# iv_sensing.net
KiCad netlist of a schematic drawn in Altium Designer
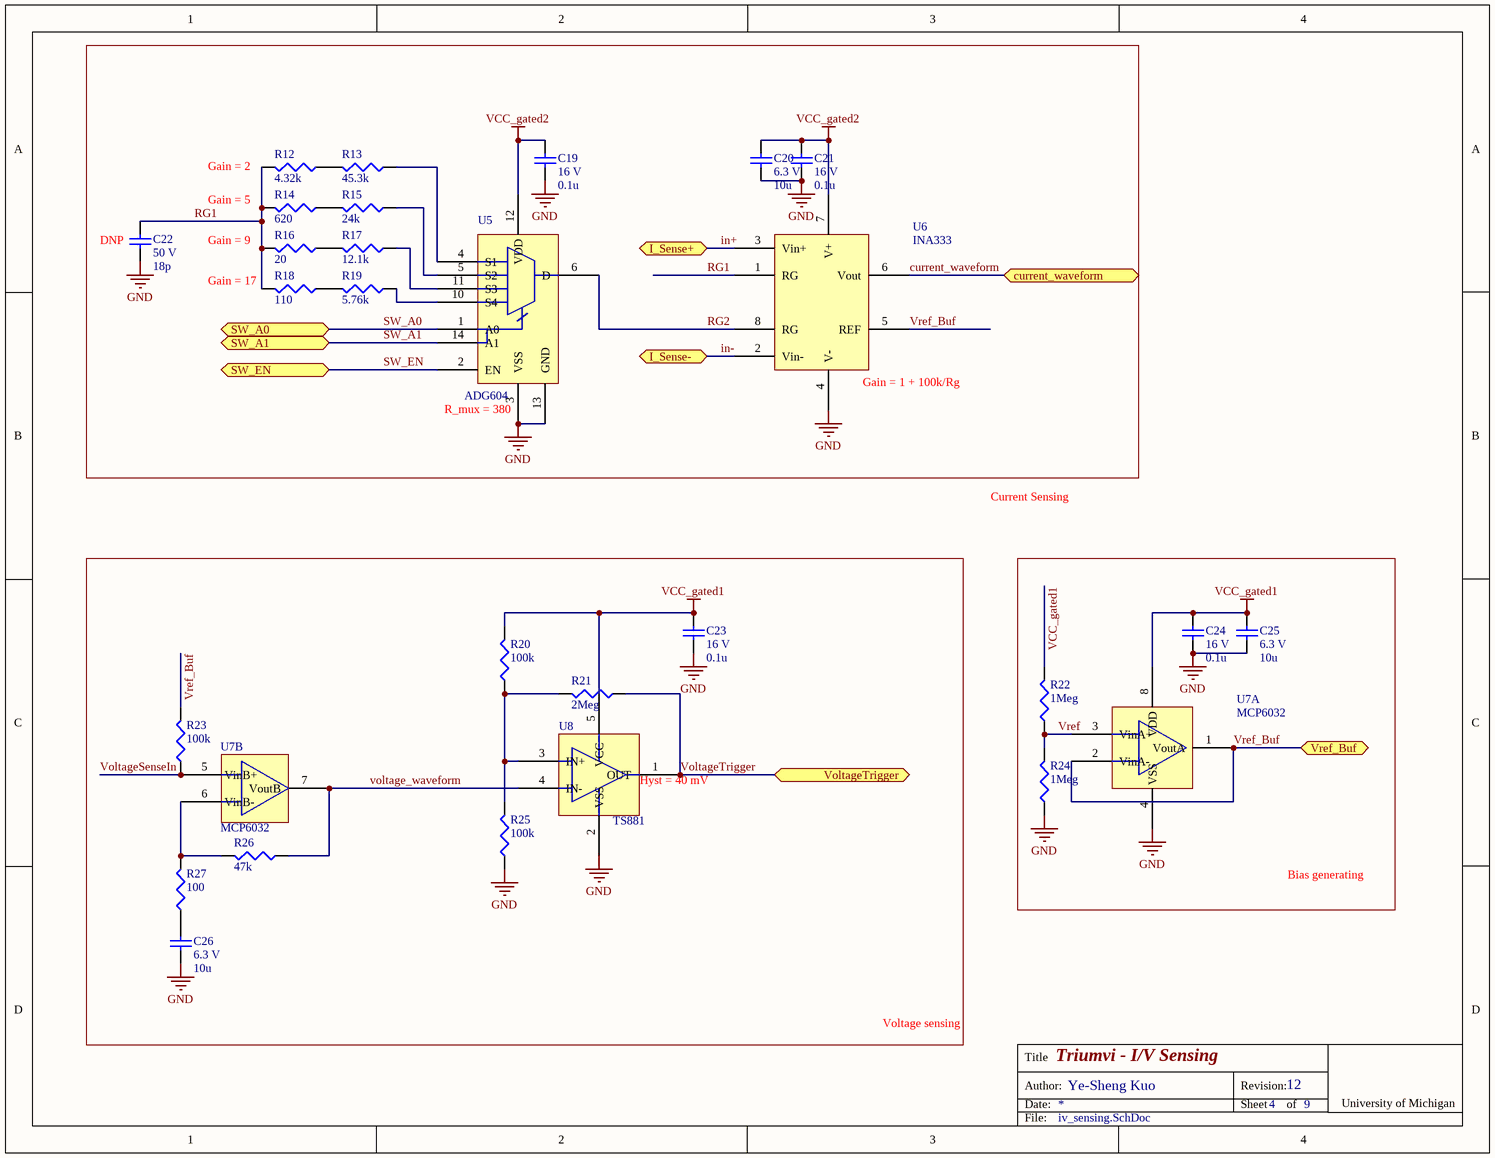
[diagram p0: iv_sensing.SchDoc]

(export (version "E")
  (design (tool "Eeschema 10.0.6"))
  (components
    (comp (ref "C19")
      (value "0.1u")
      (footprint "0402")
      (description "0.10µF ±10% 16V Ceramic Capacitor X7R 0402")
      (fields
        (field (name "VOLTAGE RATED") "16 V")
        (field (name "TOLERANCE") "10%")
        (field (name "MANUFACTURER PART NUMBER") "GRM155R71C104KA88D")
      )
      (libsource (lib "capacitors") (part "GRM155R71C104KA88D"))
    )
    (comp (ref "C20")
      (value "10u")
      (footprint "0603")
      (description "10µF ±20% 6.3V Ceramic Capacitor X5R 0603")
      (fields
        (field (name "VOLTAGE RATED") "6.3 V")
        (field (name "TOLERANCE") "20%")
        (field (name "MANUFACTURER PART NUMBER") "C1608X5R0J106M080AB")
      )
      (libsource (lib "capacitors") (part "C1608X5R0J106M080AB"))
    )
    (comp (ref "C21")
      (value "0.1u")
      (footprint "0402")
      (description "0.10µF ±10% 16V Ceramic Capacitor X7R 0402")
      (fields
        (field (name "VOLTAGE RATED") "16 V")
        (field (name "TOLERANCE") "10%")
        (field (name "MANUFACTURER PART NUMBER") "GRM155R71C104KA88D")
      )
      (libsource (lib "capacitors") (part "GRM155R71C104KA88D"))
    )
    (comp (ref "C22")
      (value "18p")
      (footprint "0402")
      (description "18pF ±2% 50V Ceramic Capacitor C0G, NP0 0402")
      (fields
        (field (name "TOLERANCE") "2%")
        (field (name "MANUFACTURER PART NUMBER") "500R07S180GV4T")
        (field (name "VOLTAGE RATED") "50 V")
      )
      (libsource (lib "capacitors") (part "500R07S180GV4T"))
    )
    (comp (ref "C23")
      (value "0.1u")
      (footprint "0402")
      (description "0.10µF ±10% 16V Ceramic Capacitor X7R 0402")
      (fields
        (field (name "VOLTAGE RATED") "16 V")
        (field (name "TOLERANCE") "10%")
        (field (name "MANUFACTURER PART NUMBER") "GRM155R71C104KA88D")
      )
      (libsource (lib "capacitors") (part "GRM155R71C104KA88D"))
    )
    (comp (ref "C24")
      (value "0.1u")
      (footprint "0402")
      (description "0.10µF ±10% 16V Ceramic Capacitor X7R 0402")
      (fields
        (field (name "VOLTAGE RATED") "16 V")
        (field (name "TOLERANCE") "10%")
        (field (name "MANUFACTURER PART NUMBER") "GRM155R71C104KA88D")
      )
      (libsource (lib "capacitors") (part "GRM155R71C104KA88D"))
    )
    (comp (ref "C25")
      (value "10u")
      (footprint "0603")
      (description "10µF ±20% 6.3V Ceramic Capacitor X5R 0603")
      (fields
        (field (name "VOLTAGE RATED") "6.3 V")
        (field (name "TOLERANCE") "20%")
        (field (name "MANUFACTURER PART NUMBER") "C1608X5R0J106M080AB")
      )
      (libsource (lib "capacitors") (part "C1608X5R0J106M080AB"))
    )
    (comp (ref "C26")
      (value "10u")
      (footprint "0603")
      (description "10µF ±20% 6.3V Ceramic Capacitor X5R 0603")
      (fields
        (field (name "VOLTAGE RATED") "6.3 V")
        (field (name "TOLERANCE") "20%")
        (field (name "MANUFACTURER PART NUMBER") "C1608X5R0J106M080AB")
      )
      (libsource (lib "capacitors") (part "C1608X5R0J106M080AB"))
    )
    (comp (ref "R12")
      (value "4.32k")
      (footprint "0402")
      (description "RES SMD 4.32K OHM 1% 1/16W 0402")
      (fields
        (field (name "MANUFACTURER PART NUMBER") "CRCW04024K32FKED")
        (field (name "MANUFACTURER") "Vishay Dale")
      )
      (libsource (lib "resistors") (part "CRCW04024K32FKED"))
    )
    (comp (ref "R13")
      (value "45.3k")
      (footprint "0402")
      (description "RES SMD 45.3KOHM 0.5% 1/16W 0402")
      (fields
        (field (name "MANUFACTURER PART NUMBER") "RT0402DRD0745K3L")
        (field (name "MANUFACTURER") "Yageo")
      )
      (libsource (lib "resistors") (part "RT0402DRD0745K3L"))
    )
    (comp (ref "R14")
      (value "620")
      (footprint "0402")
      (description "RES SMD 620 OHM 1% 1/16W 0402")
      (fields
        (field (name "MANUFACTURER PART NUMBER") "CRCW0402620RFKED")
        (field (name "MANUFACTURER") "Vishay Dale")
      )
      (libsource (lib "resistors") (part "CRCW0402620RFKED"))
    )
    (comp (ref "R15")
      (value "24k")
      (footprint "0402")
      (description "RES SMD 24K OHM 0.5% 1/16W 0402")
      (fields
        (field (name "MANUFACTURER PART NUMBER") "RT0402DRE0724KL")
        (field (name "MANUFACTURER") "Yageo")
      )
      (libsource (lib "resistors") (part "RT0402DRE0724KL"))
    )
    (comp (ref "R16")
      (value "20")
      (footprint "0402")
      (description "RES SMD 20 OHM 1% 1/16W 0402")
      (fields
        (field (name "MANUFACTURER PART NUMBER") "CRCW040220R0FKED")
        (field (name "MANUFACTURER") "Vishay Dale")
      )
      (libsource (lib "resistors") (part "CRCW040220R0FKED"))
    )
    (comp (ref "R17")
      (value "12.1k")
      (footprint "0402")
      (description "RES SMD 12.1K OHM 1% 1/16W 0402")
      (fields
        (field (name "MANUFACTURER PART NUMBER") "CRCW040212K1FKED")
        (field (name "MANUFACTURER") "Vishay Dale")
      )
      (libsource (lib "resistors") (part "CRCW040212K1FKED"))
    )
    (comp (ref "R18")
      (value "110")
      (footprint "0402")
      (description "RES SMD 110 OHM 1% 1/16W 0402")
      (fields
        (field (name "MANUFACTURER PART NUMBER") "CRCW0402110RFKED")
        (field (name "MANUFACTURER") "Vishay Dale")
      )
      (libsource (lib "resistors") (part "CRCW0402110RFKED"))
    )
    (comp (ref "R19")
      (value "5.76k")
      (footprint "0402")
      (description "RES SMD 5.76K OHM 0.5% 1/16W 0402")
      (fields
        (field (name "MANUFACTURER PART NUMBER") "RC0402FR-075K76L")
        (field (name "MANUFACTURER") "Yageo")
      )
      (libsource (lib "resistors") (part "RC0402FR-075K76L"))
    )
    (comp (ref "R20")
      (value "100k")
      (footprint "0402")
      (description "RES SMD 100K OHM 1% 1/16W 0402")
      (fields (field (name "TOLERANCE") "1%") (field (name "POWER") "1/16 W"))
      (libsource (lib "resistors") (part "CRCW0402100KFKED"))
    )
    (comp (ref "R21")
      (value "2Meg")
      (footprint "0402")
      (description "RES SMD 2M OHM 1% 1/16W 0402")
      (fields (field (name "TOLERANCE") "1%") (field (name "POWER") "1/16 W"))
      (libsource (lib "resistors") (part "CRCW04022M00FKED"))
    )
    (comp (ref "R22")
      (value "1Meg")
      (footprint "0402")
      (description "RES SMD 1M OHM 1% 1/16W 0402")
      (fields (field (name "TOLERANCE") "1%") (field (name "POWER") "1/16 W"))
      (libsource (lib "resistors") (part "CRCW04021M00FKED"))
    )
    (comp (ref "R23")
      (value "100k")
      (footprint "0402")
      (description "RES SMD 100K OHM 1% 1/16W 0402")
      (fields (field (name "TOLERANCE") "1%") (field (name "POWER") "1/16 W"))
      (libsource (lib "resistors") (part "CRCW0402100KFKED"))
    )
    (comp (ref "R24")
      (value "1Meg")
      (footprint "0402")
      (description "RES SMD 1M OHM 1% 1/16W 0402")
      (fields (field (name "TOLERANCE") "1%") (field (name "POWER") "1/16 W"))
      (libsource (lib "resistors") (part "CRCW04021M00FKED"))
    )
    (comp (ref "R25")
      (value "100k")
      (footprint "0402")
      (description "RES SMD 100K OHM 1% 1/16W 0402")
      (fields (field (name "TOLERANCE") "1%") (field (name "POWER") "1/16 W"))
      (libsource (lib "resistors") (part "CRCW0402100KFKED"))
    )
    (comp (ref "R26")
      (value "47k")
      (footprint "0402")
      (description "RES SMD 47K OHM 1% 1/16W 0402")
      (fields (field (name "TOLERANCE") "1%") (field (name "POWER") "1/16 W"))
      (libsource (lib "resistors") (part "CRCW040247K0FKED"))
    )
    (comp (ref "R27")
      (value "100")
      (footprint "0402")
      (description "RES SMD 100 OHM 1% 1/16W 0402")
      (fields (field (name "TOLERANCE") "1%") (field (name "POWER") "1/16 W"))
      (libsource (lib "resistors") (part "CRCW0402100RFKED"))
    )
    (comp (ref "U5")
      (value "ADG604")
      (footprint "TSSOP-14")
      (description "1 pC Charge Injection, 100 pA Leakage  CMOS  5 V/5 V/3 V 4-Channel Multiplexer")
      (libsource (lib "multiplexer") (part "ADG604"))
    )
    (comp (ref "U6")
      (value "INA333")
      (footprint "MSOP-8")
      (description "Micro-Power (50uA), Zero-Drift, Rail-to-Rail Out  Instrumentation Amplifier")
      (libsource (lib "amplifier") (part "INA333"))
    )
    (comp (ref "U7")
      (value "MCP6032")
      (footprint "MSOP-8")
      (description "0.9 µA, High Precision Op Amps")
      (libsource (lib "amplifier") (part "MCP6032"))
    )
    (comp (ref "U8")
      (value "TS881")
      (footprint "SC70-5")
      (description "Rail-to-rail 0.9 V nanopower comparator")
      (libsource (lib "comparators") (part "TS881"))
    )
  )
  (nets
    (net (code "1") (name "/RG1") (class "Default")
      (node (ref "C22") (pin "1") (pintype "passive"))
      (node (ref "R12") (pin "1") (pintype "passive"))
      (node (ref "R14") (pin "1") (pintype "passive"))
      (node (ref "R16") (pin "1") (pintype "passive"))
      (node (ref "R18") (pin "1") (pintype "passive"))
      (node (ref "U6") (pin "1") (pinfunction "RG_1") (pintype "passive"))
    )
    (net (code "2") (name "/RG2") (class "Default")
      (node (ref "U5") (pin "6") (pinfunction "D_6") (pintype "passive"))
      (node (ref "U6") (pin "8") (pinfunction "RG_8") (pintype "passive"))
    )
    (net (code "3") (name "/SW_A0") (class "Default")
      (node (ref "U5") (pin "1") (pinfunction "A0_1") (pintype "passive"))
    )
    (net (code "4") (name "/SW_A1") (class "Default")
      (node (ref "U5") (pin "14") (pinfunction "A1_14") (pintype "passive"))
    )
    (net (code "5") (name "/SW_EN") (class "Default")
      (node (ref "U5") (pin "2") (pinfunction "EN_2") (pintype "passive"))
    )
    (net (code "6") (name "/VoltageSenseIn") (class "Default")
      (node (ref "R23") (pin "2") (pintype "passive"))
      (node (ref "U7") (pin "5") (pinfunction "VinB+_5") (pintype "passive"))
    )
    (net (code "7") (name "/VoltageTrigger") (class "Default")
      (node (ref "R21") (pin "2") (pintype "passive"))
      (node (ref "U8") (pin "1") (pinfunction "OUT_1") (pintype "passive"))
    )
    (net (code "8") (name "/Vref") (class "Default")
      (node (ref "R22") (pin "2") (pintype "passive"))
      (node (ref "R24") (pin "1") (pintype "passive"))
      (node (ref "U7") (pin "3") (pinfunction "VinA+_3") (pintype "passive"))
    )
    (net (code "9") (name "/Vref_Buf") (class "Default")
      (node (ref "R23") (pin "1") (pintype "passive"))
      (node (ref "U6") (pin "5") (pinfunction "REF_5") (pintype "passive"))
      (node (ref "U7") (pin "1") (pinfunction "VoutA_1") (pintype "passive"))
      (node (ref "U7") (pin "2") (pinfunction "VinA-_2") (pintype "passive"))
    )
    (net (code "10") (name "/current_waveform") (class "Default")
      (node (ref "U6") (pin "6") (pinfunction "Vout_6") (pintype "passive"))
    )
    (net (code "11") (name "/in+") (class "Default")
      (node (ref "U6") (pin "3") (pinfunction "Vin+_3") (pintype "passive"))
    )
    (net (code "12") (name "/in-") (class "Default")
      (node (ref "U6") (pin "2") (pinfunction "Vin-_2") (pintype "passive"))
    )
    (net (code "13") (name "/voltage_waveform") (class "Default")
      (node (ref "R26") (pin "2") (pintype "passive"))
      (node (ref "U7") (pin "7") (pinfunction "VoutB_7") (pintype "passive"))
      (node (ref "U8") (pin "4") (pinfunction "IN-_4") (pintype "passive"))
    )
    (net (code "14") (name "GND") (class "Default")
      (node (ref "C19") (pin "2") (pintype "passive"))
      (node (ref "C20") (pin "2") (pintype "passive"))
      (node (ref "C21") (pin "2") (pintype "passive"))
      (node (ref "C22") (pin "2") (pintype "passive"))
      (node (ref "C23") (pin "2") (pintype "passive"))
      (node (ref "C24") (pin "2") (pintype "passive"))
      (node (ref "C25") (pin "2") (pintype "passive"))
      (node (ref "C26") (pin "2") (pintype "passive"))
      (node (ref "R24") (pin "2") (pintype "passive"))
      (node (ref "R25") (pin "2") (pintype "passive"))
      (node (ref "U5") (pin "13") (pinfunction "GND_13") (pintype "passive"))
      (node (ref "U5") (pin "3") (pinfunction "VSS_3") (pintype "passive"))
      (node (ref "U6") (pin "4") (pinfunction "V-_4") (pintype "passive"))
      (node (ref "U7") (pin "4") (pinfunction "VSS_4") (pintype "passive"))
      (node (ref "U8") (pin "2") (pinfunction "VSS_2") (pintype "passive"))
    )
    (net (code "15") (name "Net-(C26-Pad1)") (class "Default")
      (node (ref "C26") (pin "1") (pintype "passive"))
      (node (ref "R27") (pin "2") (pintype "passive"))
    )
    (net (code "16") (name "Net-(R12-Pad2)") (class "Default")
      (node (ref "R12") (pin "2") (pintype "passive"))
      (node (ref "R13") (pin "1") (pintype "passive"))
    )
    (net (code "17") (name "Net-(R14-Pad2)") (class "Default")
      (node (ref "R14") (pin "2") (pintype "passive"))
      (node (ref "R15") (pin "1") (pintype "passive"))
    )
    (net (code "18") (name "Net-(R16-Pad2)") (class "Default")
      (node (ref "R16") (pin "2") (pintype "passive"))
      (node (ref "R17") (pin "1") (pintype "passive"))
    )
    (net (code "19") (name "Net-(R18-Pad2)") (class "Default")
      (node (ref "R18") (pin "2") (pintype "passive"))
      (node (ref "R19") (pin "1") (pintype "passive"))
    )
    (net (code "20") (name "Net-(U5-S1)") (class "Default")
      (node (ref "R13") (pin "2") (pintype "passive"))
      (node (ref "U5") (pin "4") (pinfunction "S1_4") (pintype "passive"))
    )
    (net (code "21") (name "Net-(U5-S2)") (class "Default")
      (node (ref "R15") (pin "2") (pintype "passive"))
      (node (ref "U5") (pin "5") (pinfunction "S2_5") (pintype "passive"))
    )
    (net (code "22") (name "Net-(U5-S3)") (class "Default")
      (node (ref "R17") (pin "2") (pintype "passive"))
      (node (ref "U5") (pin "11") (pinfunction "S3_11") (pintype "passive"))
    )
    (net (code "23") (name "Net-(U5-S4)") (class "Default")
      (node (ref "R19") (pin "2") (pintype "passive"))
      (node (ref "U5") (pin "10") (pinfunction "S4_10") (pintype "passive"))
    )
    (net (code "24") (name "Net-(U7B-VinB-)") (class "Default")
      (node (ref "R26") (pin "1") (pintype "passive"))
      (node (ref "R27") (pin "1") (pintype "passive"))
      (node (ref "U7") (pin "6") (pinfunction "VinB-_6") (pintype "passive"))
    )
    (net (code "25") (name "Net-(U8-IN+)") (class "Default")
      (node (ref "R20") (pin "2") (pintype "passive"))
      (node (ref "R21") (pin "1") (pintype "passive"))
      (node (ref "R25") (pin "1") (pintype "passive"))
      (node (ref "U8") (pin "3") (pinfunction "IN+_3") (pintype "passive"))
    )
    (net (code "26") (name "VCC_gated1") (class "Default")
      (node (ref "C23") (pin "1") (pintype "passive"))
      (node (ref "C24") (pin "1") (pintype "passive"))
      (node (ref "C25") (pin "1") (pintype "passive"))
      (node (ref "R20") (pin "1") (pintype "passive"))
      (node (ref "R22") (pin "1") (pintype "passive"))
      (node (ref "U7") (pin "8") (pinfunction "VDD_8") (pintype "passive"))
      (node (ref "U8") (pin "5") (pinfunction "VCC_5") (pintype "passive"))
    )
    (net (code "27") (name "VCC_gated2") (class "Default")
      (node (ref "C19") (pin "1") (pintype "passive"))
      (node (ref "C20") (pin "1") (pintype "passive"))
      (node (ref "C21") (pin "1") (pintype "passive"))
      (node (ref "U5") (pin "12") (pinfunction "VDD_12") (pintype "passive"))
      (node (ref "U6") (pin "7") (pinfunction "V+_7") (pintype "passive"))
    )
  )
)
